# Pyro_Channel.net
KiCad netlist of a schematic drawn in Altium Designer
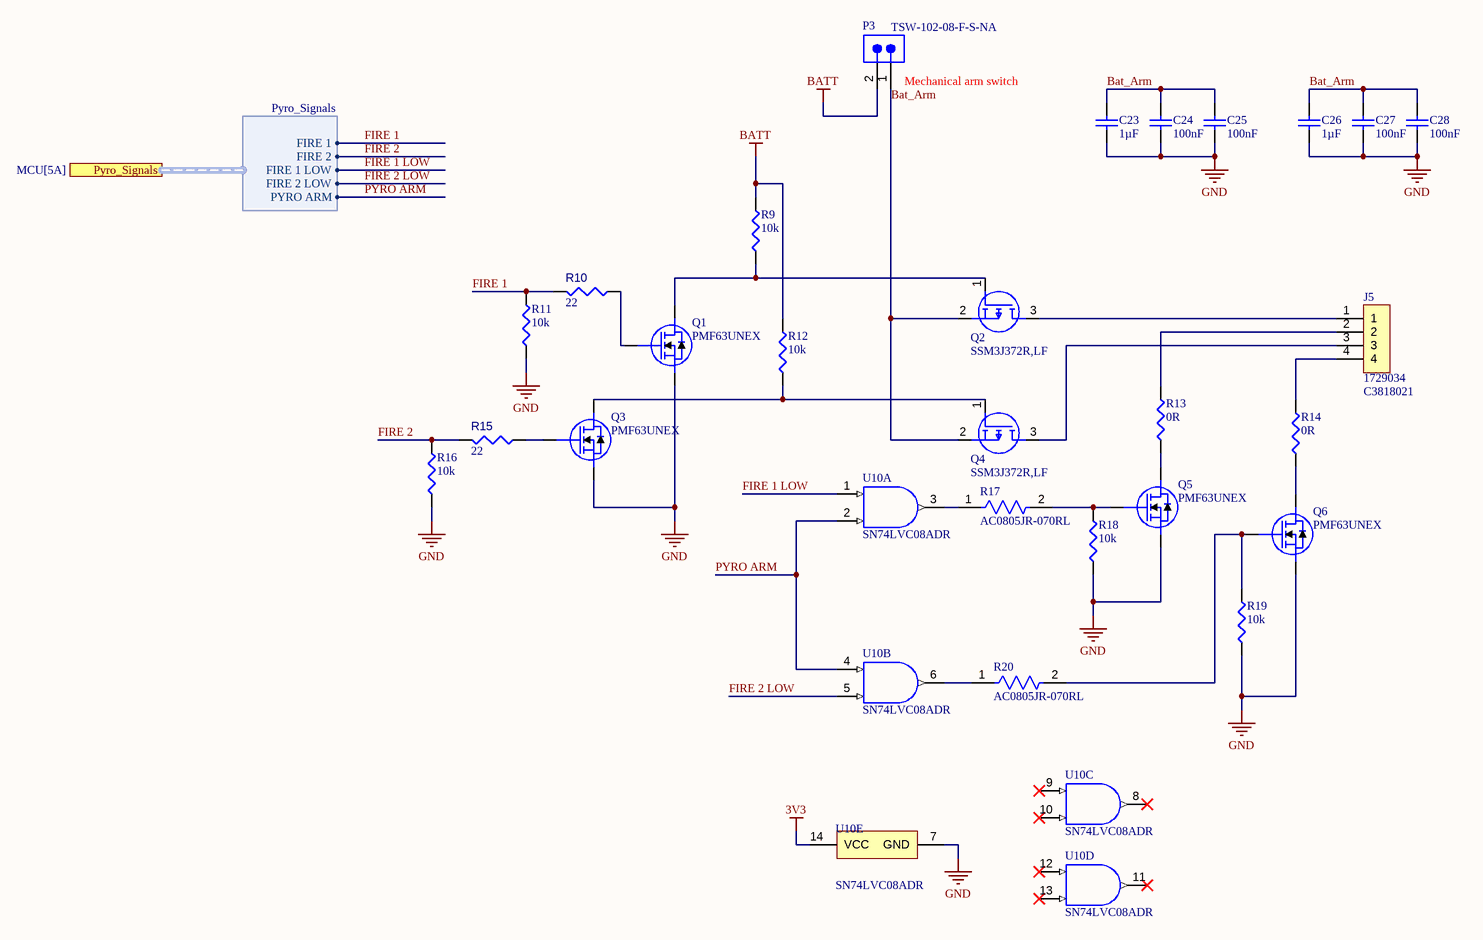
[diagram p0: Pyro_Channel.SchDoc]

(export (version "E")
  (design (tool "Eeschema 10.0.6"))
  (components
    (comp (ref "C23")
      (value "1µF")
      (footprint "0402_C")
      (fields
        (field (name "TOLERANCE") "1%")
        (field (name "POWER") "62.5mW")
        (field (name "LCSC PART NUMBER") "C307413")
        (field (name "SOURCE") "Hybrids_Avionics.SCHLIB")
      )
      (libsource (lib "Americas - Purdue University - Purdue Space Program Hybrids") (part "UMK105B7104KV-FR"))
    )
    (comp (ref "C24")
      (value "100nF")
      (footprint "0402_C")
      (fields
        (field (name "MANUFACTURER") "Samsung Electro-Mechanics")
        (field (name "MANUFACTURER PART NUMBER") "CL05B104KO5NNNC")
        (field (name "TOLERANCE") "10%")
      )
      (libsource (lib "Flight_Computer1") (part "C_100nF_0402"))
    )
    (comp (ref "C25")
      (value "100nF")
      (footprint "0402_C")
      (fields
        (field (name "MANUFACTURER") "Samsung Electro-Mechanics")
        (field (name "MANUFACTURER PART NUMBER") "CL05B104KO5NNNC")
        (field (name "TOLERANCE") "10%")
      )
      (libsource (lib "Flight_Computer1") (part "C_100nF_0402"))
    )
    (comp (ref "C26")
      (value "1µF")
      (footprint "0402_C")
      (fields
        (field (name "TOLERANCE") "1%")
        (field (name "POWER") "62.5mW")
        (field (name "LCSC PART NUMBER") "C307413")
        (field (name "SOURCE") "Hybrids_Avionics.SCHLIB")
      )
      (libsource (lib "Americas - Purdue University - Purdue Space Program Hybrids") (part "UMK105B7104KV-FR"))
    )
    (comp (ref "C27")
      (value "100nF")
      (footprint "0402_C")
      (fields
        (field (name "MANUFACTURER") "Samsung Electro-Mechanics")
        (field (name "MANUFACTURER PART NUMBER") "CL05B104KO5NNNC")
        (field (name "TOLERANCE") "10%")
      )
      (libsource (lib "Flight_Computer1") (part "C_100nF_0402"))
    )
    (comp (ref "C28")
      (value "100nF")
      (footprint "0402_C")
      (fields
        (field (name "MANUFACTURER") "Samsung Electro-Mechanics")
        (field (name "MANUFACTURER PART NUMBER") "CL05B104KO5NNNC")
        (field (name "TOLERANCE") "10%")
      )
      (libsource (lib "Flight_Computer1") (part "C_100nF_0402"))
    )
    (comp (ref "J5")
      (value "1729034")
      (footprint "1729034")
      (description "TERM BLK 4POS SIDE ENTRY 5MM PCB")
      (fields
        (field (name "LCSC PART NUMBER") "C3818021")
        (field (name "MANUFACTURER") "Phoenix Contact")
        (field (name "SOURCE") "Hybrids_Avionics.SCHLIB")
        (field (name "SAFETY APPROVAL") "UL")
      )
      (libsource (lib "Americas - Purdue University - Purdue Space Program Hybrids") (part "1729034"))
    )
    (comp (ref "P3")
      (value "TSW-102-08-F-S-NA")
      (footprint "SMTC-TSW-102-08-X-S-NA")
      (fields (field (name "MANUFACTURER") "Samtec"))
      (libsource (lib "Altium Content Vault") (part "SMTC-TSW-102-X-X-S-X"))
    )
    (comp (ref "Q1")
      (value "PMF63UNEX")
      (footprint "PMF63UNEX-Footprint-1")
      (description "MOSFET N-CH 20V 2.2A SOT323")
      (libsource (lib "Americas - Purdue University - Purdue Space Program Hybrids") (part "N-CHANNEL 20 V (D-S) MOSFET SOT--Symbol-1"))
    )
    (comp (ref "Q2")
      (value "SSM3J372R,LF")
      (footprint "SSM3J372RLF")
      (description "MOSFET (P-Channel)")
      (fields
        (field (name "MOUSER PART NUMBER") "757-SSM3J372RLF")
        (field (name "SOURCE") "Hybrids_Avionics.SCHLIB")
      )
      (libsource (lib "Americas - Purdue University - Purdue Space Program Hybrids") (part "SSM3J372R,LF"))
    )
    (comp (ref "Q3")
      (value "PMF63UNEX")
      (footprint "PMF63UNEX-Footprint-1")
      (description "MOSFET N-CH 20V 2.2A SOT323")
      (libsource (lib "Americas - Purdue University - Purdue Space Program Hybrids") (part "N-CHANNEL 20 V (D-S) MOSFET SOT--Symbol-1"))
    )
    (comp (ref "Q4")
      (value "SSM3J372R,LF")
      (footprint "SSM3J372RLF")
      (description "MOSFET (P-Channel)")
      (fields
        (field (name "MOUSER PART NUMBER") "757-SSM3J372RLF")
        (field (name "SOURCE") "Hybrids_Avionics.SCHLIB")
      )
      (libsource (lib "Americas - Purdue University - Purdue Space Program Hybrids") (part "SSM3J372R,LF"))
    )
    (comp (ref "Q5")
      (value "PMF63UNEX")
      (footprint "PMF63UNEX-Footprint-1")
      (description "MOSFET N-CH 20V 2.2A SOT323")
      (libsource (lib "Americas - Purdue University - Purdue Space Program Hybrids") (part "N-CHANNEL 20 V (D-S) MOSFET SOT--Symbol-1"))
    )
    (comp (ref "Q6")
      (value "PMF63UNEX")
      (footprint "PMF63UNEX-Footprint-1")
      (description "MOSFET N-CH 20V 2.2A SOT323")
      (libsource (lib "Americas - Purdue University - Purdue Space Program Hybrids") (part "N-CHANNEL 20 V (D-S) MOSFET SOT--Symbol-1"))
    )
    (comp (ref "R9")
      (value "10k")
      (footprint "0402_R")
      (description "RES SMD 10K OHM 0.1% 1/16W 0402")
      (fields (field (name "LCSC PART #") "C191915") (field (name "MANUFACTURER") "Yageo Group"))
      (libsource (lib "Flight_Computer1") (part "R_10k_0402"))
    )
    (comp (ref "R10")
      (value "22")
      (footprint "RESC0402(1005)_L")
      (description "Chip Resistor, 22 Ohms, +/-5 %, 63 mW, -55 to 155 degC, 0402")
      (fields (field (name "TOLERANCE") "5%") (field (name "POWER") "63mW"))
      (libsource (lib "Americas - Purdue University - Purdue Space Program Hybrids") (part "RES-2"))
    )
    (comp (ref "R11")
      (value "10k")
      (footprint "0402_R")
      (description "RES SMD 10K OHM 0.1% 1/16W 0402")
      (fields (field (name "LCSC PART #") "C191915") (field (name "MANUFACTURER") "Yageo Group"))
      (libsource (lib "Flight_Computer1") (part "R_10k_0402"))
    )
    (comp (ref "R12")
      (value "10k")
      (footprint "0402_R")
      (description "RES SMD 10K OHM 0.1% 1/16W 0402")
      (fields (field (name "LCSC PART #") "C191915") (field (name "MANUFACTURER") "Yageo Group"))
      (libsource (lib "Flight_Computer1") (part "R_10k_0402"))
    )
    (comp (ref "R13")
      (value "0R")
      (footprint "0402_R")
      (description "GENERAL PURPOSE CHIP RESISTOR Metal Glaze/thick Film, 0.0625W, 0ohm, Surface Mount, 0402")
      (fields
        (field (name "MANUFACTURER") "Yageo Group")
        (field (name "MANUFACTURER PART NUMBER") "RC0402JR-070RL")
      )
      (libsource (lib "Schlib1") (part "R_0R_0402"))
    )
    (comp (ref "R14")
      (value "0R")
      (footprint "0402_R")
      (description "GENERAL PURPOSE CHIP RESISTOR Metal Glaze/thick Film, 0.0625W, 0ohm, Surface Mount, 0402")
      (fields
        (field (name "MANUFACTURER") "Yageo Group")
        (field (name "MANUFACTURER PART NUMBER") "RC0402JR-070RL")
      )
      (libsource (lib "Schlib1") (part "R_0R_0402"))
    )
    (comp (ref "R15")
      (value "22")
      (footprint "RESC0402(1005)_L")
      (description "Chip Resistor, 22 Ohms, +/-5 %, 63 mW, -55 to 155 degC, 0402")
      (fields (field (name "TOLERANCE") "5%") (field (name "POWER") "63mW"))
      (libsource (lib "Americas - Purdue University - Purdue Space Program Hybrids") (part "RES-2"))
    )
    (comp (ref "R16")
      (value "10k")
      (footprint "0402_R")
      (description "RES SMD 10K OHM 0.1% 1/16W 0402")
      (fields (field (name "LCSC PART #") "C191915") (field (name "MANUFACTURER") "Yageo Group"))
      (libsource (lib "Flight_Computer1") (part "R_10k_0402"))
    )
    (comp (ref "R17")
      (value "AC0805JR-070RL")
      (footprint "FP-AC0805-0_6-MFG")
      (description "RES SMD 0 OHM JUMPER 1/8W 0805")
      (fields (field (name "TOLERANCE") "5%"))
      (libsource (lib "Altium Content Vault") (part "1029c3af85768c4190bb7ad29bc67b5"))
    )
    (comp (ref "R18")
      (value "10k")
      (footprint "0402_R")
      (description "RES SMD 10K OHM 0.1% 1/16W 0402")
      (fields (field (name "LCSC PART #") "C191915") (field (name "MANUFACTURER") "Yageo Group"))
      (libsource (lib "Flight_Computer1") (part "R_10k_0402"))
    )
    (comp (ref "R19")
      (value "10k")
      (footprint "0402_R")
      (description "RES SMD 10K OHM 0.1% 1/16W 0402")
      (fields (field (name "LCSC PART #") "C191915") (field (name "MANUFACTURER") "Yageo Group"))
      (libsource (lib "Flight_Computer1") (part "R_10k_0402"))
    )
    (comp (ref "R20")
      (value "AC0805JR-070RL")
      (footprint "FP-AC0805-0_6-MFG")
      (description "RES SMD 0 OHM JUMPER 1/8W 0805")
      (fields (field (name "TOLERANCE") "5%"))
      (libsource (lib "Altium Content Vault") (part "1029c3af85768c4190bb7ad29bc67b5"))
    )
    (comp (ref "U10")
      (value "SN74LVC08ADR")
      (footprint "D0014A_N")
      (description "Quadruple 2-Input Positive-AND Gate, D0014A, LARGE T&R")
      (fields
        (field (name "MANUFACTURER") "Texas Instruments")
        (field (name "GENERIC PART NUMBER") "SN74LVC08A")
      )
      (libsource (lib "Altium Content Vault") (part "TI-AND-4-2IN-14"))
    )
  )
  (nets
    (net (code "2") (name "/Bat_Arm") (class "Default")
      (node (ref "C23") (pin "2") (pinfunction "2_2") (pintype "passive"))
      (node (ref "C24") (pin "2") (pinfunction "2_2") (pintype "passive"))
      (node (ref "C25") (pin "2") (pinfunction "2_2") (pintype "passive"))
      (node (ref "C26") (pin "2") (pinfunction "2_2") (pintype "passive"))
      (node (ref "C27") (pin "2") (pinfunction "2_2") (pintype "passive"))
      (node (ref "C28") (pin "2") (pinfunction "2_2") (pintype "passive"))
      (node (ref "P3") (pin "1") (pinfunction "1_1") (pintype "passive"))
      (node (ref "Q2") (pin "2") (pinfunction "S_2") (pintype "passive"))
      (node (ref "Q4") (pin "2") (pinfunction "S_2") (pintype "passive"))
    )
    (net (code "3") (name "/FIRE 1") (class "Default")
      (node (ref "R10") (pin "2") (pinfunction "2_2") (pintype "passive"))
      (node (ref "R11") (pin "2") (pinfunction "2_2") (pintype "passive"))
    )
    (net (code "4") (name "/FIRE 1 LOW") (class "Default")
      (node (ref "U10") (pin "1") (pinfunction "1A_1") (pintype "input"))
    )
    (net (code "5") (name "/FIRE 2") (class "Default")
      (node (ref "R15") (pin "2") (pinfunction "2_2") (pintype "passive"))
      (node (ref "R16") (pin "2") (pinfunction "2_2") (pintype "passive"))
    )
    (net (code "6") (name "/FIRE 2 LOW") (class "Default")
      (node (ref "U10") (pin "5") (pinfunction "2B_5") (pintype "input"))
    )
    (net (code "7") (name "/PYRO ARM") (class "Default")
      (node (ref "U10") (pin "2") (pinfunction "1B_2") (pintype "input"))
      (node (ref "U10") (pin "4") (pinfunction "2A_4") (pintype "input"))
    )
    (net (code "9") (name "3V3") (class "Default")
      (node (ref "U10") (pin "14") (pinfunction "VCC_14") (pintype "power_in"))
    )
    (net (code "10") (name "BATT") (class "Default")
      (node (ref "P3") (pin "2") (pinfunction "2_2") (pintype "passive"))
      (node (ref "R12") (pin "1") (pinfunction "1_1") (pintype "passive"))
      (node (ref "R9") (pin "1") (pinfunction "1_1") (pintype "passive"))
    )
    (net (code "11") (name "GND") (class "Default")
      (node (ref "C23") (pin "1") (pinfunction "1_1") (pintype "passive"))
      (node (ref "C24") (pin "1") (pinfunction "1_1") (pintype "passive"))
      (node (ref "C25") (pin "1") (pinfunction "1_1") (pintype "passive"))
      (node (ref "C26") (pin "1") (pinfunction "1_1") (pintype "passive"))
      (node (ref "C27") (pin "1") (pinfunction "1_1") (pintype "passive"))
      (node (ref "C28") (pin "1") (pinfunction "1_1") (pintype "passive"))
      (node (ref "Q1") (pin "3") (pinfunction "S_3") (pintype "passive"))
      (node (ref "Q3") (pin "3") (pinfunction "S_3") (pintype "passive"))
      (node (ref "Q5") (pin "3") (pinfunction "S_3") (pintype "passive"))
      (node (ref "Q6") (pin "3") (pinfunction "S_3") (pintype "passive"))
      (node (ref "R11") (pin "1") (pinfunction "1_1") (pintype "passive"))
      (node (ref "R16") (pin "1") (pinfunction "1_1") (pintype "passive"))
      (node (ref "R18") (pin "1") (pinfunction "1_1") (pintype "passive"))
      (node (ref "R19") (pin "1") (pinfunction "1_1") (pintype "passive"))
      (node (ref "U10") (pin "7") (pinfunction "GND_7") (pintype "power_in"))
    )
    (net (code "12") (name "Net-(J5-Pad2)") (class "Default")
      (node (ref "J5") (pin "2") (pinfunction "2_2") (pintype "passive"))
      (node (ref "R13") (pin "2") (pinfunction "2_2") (pintype "passive"))
    )
    (net (code "13") (name "Net-(J5-Pad4)") (class "Default")
      (node (ref "J5") (pin "4") (pinfunction "4_4") (pintype "passive"))
      (node (ref "R14") (pin "2") (pinfunction "2_2") (pintype "passive"))
    )
    (net (code "14") (name "Net-(Q1-D)") (class "Default")
      (node (ref "Q1") (pin "2") (pinfunction "D_2") (pintype "passive"))
      (node (ref "Q2") (pin "1") (pinfunction "G_1") (pintype "passive"))
      (node (ref "R9") (pin "2") (pinfunction "2_2") (pintype "passive"))
    )
    (net (code "15") (name "Net-(Q1-G)") (class "Default")
      (node (ref "Q1") (pin "1") (pinfunction "G_1") (pintype "passive"))
      (node (ref "R10") (pin "1") (pinfunction "1_1") (pintype "passive"))
    )
    (net (code "16") (name "Net-(Q2-D)") (class "Default")
      (node (ref "J5") (pin "1") (pinfunction "1_1") (pintype "passive"))
      (node (ref "Q2") (pin "3") (pinfunction "D_3") (pintype "passive"))
    )
    (net (code "17") (name "Net-(Q3-D)") (class "Default")
      (node (ref "Q3") (pin "2") (pinfunction "D_2") (pintype "passive"))
      (node (ref "Q4") (pin "1") (pinfunction "G_1") (pintype "passive"))
      (node (ref "R12") (pin "2") (pinfunction "2_2") (pintype "passive"))
    )
    (net (code "18") (name "Net-(Q3-G)") (class "Default")
      (node (ref "Q3") (pin "1") (pinfunction "G_1") (pintype "passive"))
      (node (ref "R15") (pin "1") (pinfunction "1_1") (pintype "passive"))
    )
    (net (code "19") (name "Net-(Q4-D)") (class "Default")
      (node (ref "J5") (pin "3") (pinfunction "3_3") (pintype "passive"))
      (node (ref "Q4") (pin "3") (pinfunction "D_3") (pintype "passive"))
    )
    (net (code "20") (name "Net-(Q5-D)") (class "Default")
      (node (ref "Q5") (pin "2") (pinfunction "D_2") (pintype "passive"))
      (node (ref "R13") (pin "1") (pinfunction "1_1") (pintype "passive"))
    )
    (net (code "21") (name "Net-(Q5-G)") (class "Default")
      (node (ref "Q5") (pin "1") (pinfunction "G_1") (pintype "passive"))
      (node (ref "R17") (pin "2") (pinfunction "2_2") (pintype "passive"))
      (node (ref "R18") (pin "2") (pinfunction "2_2") (pintype "passive"))
    )
    (net (code "22") (name "Net-(Q6-D)") (class "Default")
      (node (ref "Q6") (pin "2") (pinfunction "D_2") (pintype "passive"))
      (node (ref "R14") (pin "1") (pinfunction "1_1") (pintype "passive"))
    )
    (net (code "23") (name "Net-(Q6-G)") (class "Default")
      (node (ref "Q6") (pin "1") (pinfunction "G_1") (pintype "passive"))
      (node (ref "R19") (pin "2") (pinfunction "2_2") (pintype "passive"))
      (node (ref "R20") (pin "2") (pinfunction "2_2") (pintype "passive"))
    )
    (net (code "24") (name "Net-(U10A-1Y)") (class "Default")
      (node (ref "R17") (pin "1") (pinfunction "1_1") (pintype "passive"))
      (node (ref "U10") (pin "3") (pinfunction "1Y_3") (pintype "output"))
    )
    (net (code "25") (name "Net-(U10B-2Y)") (class "Default")
      (node (ref "R20") (pin "1") (pinfunction "1_1") (pintype "passive"))
      (node (ref "U10") (pin "6") (pinfunction "2Y_6") (pintype "output"))
    )
    (net (code "26") (name "unconnected-(U10C-3A-Pad9)") (class "Default")
      (node (ref "U10") (pin "9") (pinfunction "3A_9") (pintype "input+no_connect"))
    )
    (net (code "27") (name "unconnected-(U10C-3B-Pad10)") (class "Default")
      (node (ref "U10") (pin "10") (pinfunction "3B_10") (pintype "input+no_connect"))
    )
    (net (code "28") (name "unconnected-(U10C-3Y-Pad8)") (class "Default")
      (node (ref "U10") (pin "8") (pinfunction "3Y_8") (pintype "output+no_connect"))
    )
    (net (code "29") (name "unconnected-(U10D-4A-Pad12)") (class "Default")
      (node (ref "U10") (pin "12") (pinfunction "4A_12") (pintype "input+no_connect"))
    )
    (net (code "30") (name "unconnected-(U10D-4B-Pad13)") (class "Default")
      (node (ref "U10") (pin "13") (pinfunction "4B_13") (pintype "input+no_connect"))
    )
    (net (code "31") (name "unconnected-(U10D-4Y-Pad11)") (class "Default")
      (node (ref "U10") (pin "11") (pinfunction "4Y_11") (pintype "output+no_connect"))
    )
  )
)
